# DC075B_TGC_SOURCE.net
KiCad netlist of a schematic drawn in Altium Designer
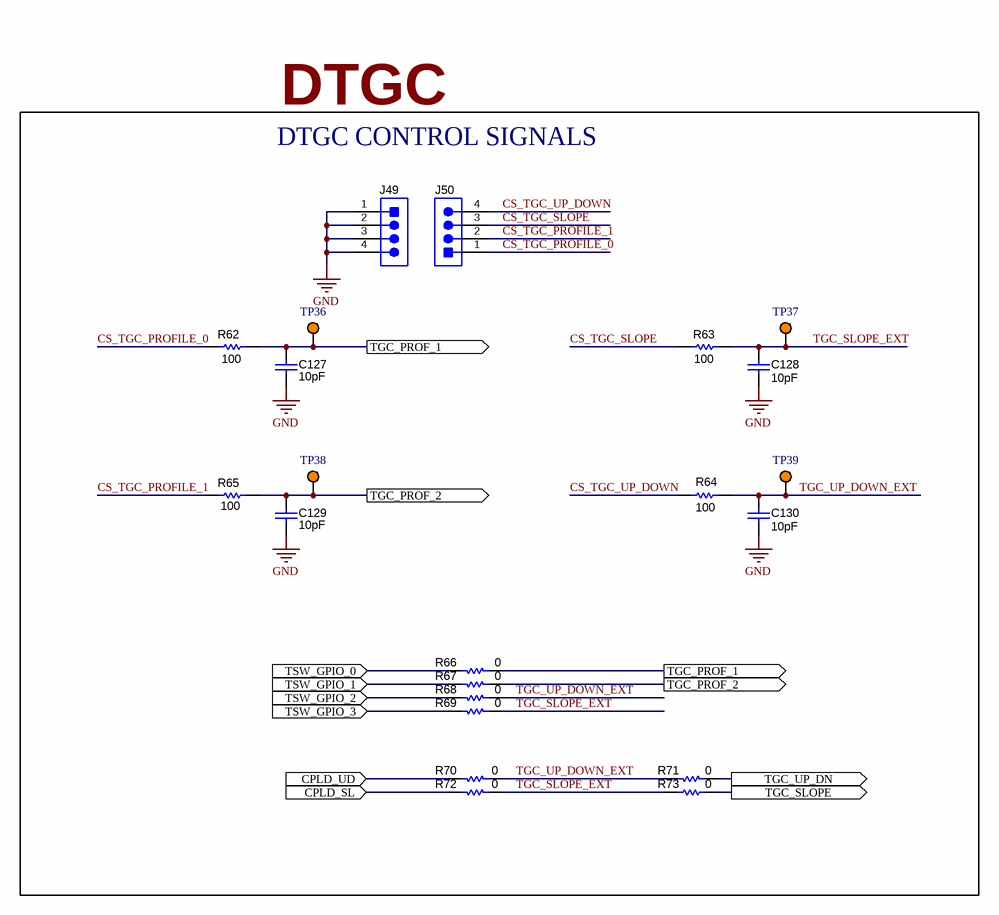
[diagram p0: DC075B_TGC_SOURCE.SchDoc]

(export (version "E")
  (design (tool "Eeschema 10.0.6"))
  (components
    (comp (ref "C127")
      (value "C0402C100C8GACTU")
      (footprint "0402")
      (description "CAP, CERM, 10 pF, 10 V,+/- 2.5%, C0G/NP0, 0402")
      (fields
        (field (name "MANUFACTURER") "Kemet")
        (field (name "VALUEDISPLAYED") "10pF")
        (field (name "PUBLISHER") "Texas Instruments")
      )
      (libsource (lib "Altium Vault - TI") (part "CMP-0064914-2"))
    )
    (comp (ref "C128")
      (value "10pF")
      (footprint "0402")
      (description "CAP, CERM, 10 pF, 50 V, +/- 5%, C0G/NP0, 0402")
      (fields
        (field (name "PARTNUMBER") "GRM1555C1H100JA01D")
        (field (name "MANUFACTURER") "MuRata")
        (field (name "PUBLISHER") "Texas Instruments")
      )
      (libsource (lib "Altium Vault - TI") (part "Capacitor"))
    )
    (comp (ref "C129")
      (value "C0402C100C8GACTU")
      (footprint "0402")
      (description "CAP, CERM, 10 pF, 10 V,+/- 2.5%, C0G/NP0, 0402")
      (fields
        (field (name "MANUFACTURER") "Kemet")
        (field (name "VALUEDISPLAYED") "10pF")
        (field (name "PUBLISHER") "Texas Instruments")
      )
      (libsource (lib "Altium Vault - TI") (part "CMP-0064914-2"))
    )
    (comp (ref "C130")
      (value "10pF")
      (footprint "0402")
      (description "CAP, CERM, 10 pF, 50 V, +/- 5%, C0G/NP0, 0402")
      (fields
        (field (name "PARTNUMBER") "GRM1555C1H100JA01D")
        (field (name "MANUFACTURER") "MuRata")
        (field (name "PUBLISHER") "Texas Instruments")
      )
      (libsource (lib "Altium Vault - TI") (part "Capacitor"))
    )
    (comp (ref "J49")
      (value "Header_4x1")
      (footprint "TSW-104-07-G-S")
      (description "Header, 100mil, 4x1, Gold, TH")
      (fields (field (name "PARTNUMBER") "TSW-104-07-G-S") (field (name "MANUFACTURER") "Samtec"))
      (libsource (lib "") (part "Header_4x1_1"))
    )
    (comp (ref "J50")
      (value "Header_4x1")
      (footprint "TSW-104-07-G-S")
      (description "Header, 100mil, 4x1, Gold, TH")
      (fields (field (name "PARTNUMBER") "TSW-104-07-G-S") (field (name "MANUFACTURER") "Samtec"))
      (libsource (lib "Altium Vault - TI") (part "Header_4x1"))
    )
    (comp (ref "R62")
      (value "100")
      (footprint "0603")
      (description "RES, 100, 1%, 0.1 W, AEC-Q200 Grade 0, 0603")
      (fields (field (name "MANUFACTURER") "Vishay-Dale") (field (name "PARTNUMBER") "CRCW0603100RFKEA"))
      (libsource (lib "Altium Vault - TI") (part "Resistor"))
    )
    (comp (ref "R63")
      (value "100")
      (footprint "0603")
      (description "RES, 100, 1%, 0.1 W, AEC-Q200 Grade 0, 0603")
      (fields (field (name "MANUFACTURER") "Vishay-Dale") (field (name "PARTNUMBER") "CRCW0603100RFKEA"))
      (libsource (lib "Altium Vault - TI") (part "Resistor"))
    )
    (comp (ref "R64")
      (value "100")
      (footprint "0603")
      (description "RES, 100, 1%, 0.1 W, AEC-Q200 Grade 0, 0603")
      (fields (field (name "MANUFACTURER") "Vishay-Dale") (field (name "PARTNUMBER") "CRCW0603100RFKEA"))
      (libsource (lib "Altium Vault - TI") (part "Resistor"))
    )
    (comp (ref "R65")
      (value "100")
      (footprint "0603")
      (description "RES, 100, 1%, 0.1 W, AEC-Q200 Grade 0, 0603")
      (fields (field (name "MANUFACTURER") "Vishay-Dale") (field (name "PARTNUMBER") "CRCW0603100RFKEA"))
      (libsource (lib "Altium Vault - TI") (part "Resistor"))
    )
    (comp (ref "R66")
      (value "0")
      (footprint "0402")
      (description "RES, 0, 5%, 0.063 W, AEC-Q200 Grade 0, 0402")
      (fields (field (name "MANUFACTURER") "Vishay-Dale") (field (name "PARTNUMBER") "CRCW04020000Z0ED"))
      (libsource (lib "Altium Vault - TI") (part "Resistor"))
    )
    (comp (ref "R67")
      (value "0")
      (footprint "0402")
      (description "RES, 0, 5%, 0.063 W, AEC-Q200 Grade 0, 0402")
      (fields (field (name "MANUFACTURER") "Vishay-Dale") (field (name "PARTNUMBER") "CRCW04020000Z0ED"))
      (libsource (lib "Altium Vault - TI") (part "Resistor"))
    )
    (comp (ref "R68")
      (value "0")
      (footprint "0402")
      (description "RES, 0, 5%, 0.063 W, AEC-Q200 Grade 0, 0402")
      (fields (field (name "MANUFACTURER") "Vishay-Dale") (field (name "PARTNUMBER") "CRCW04020000Z0ED"))
      (libsource (lib "Altium Vault - TI") (part "Resistor"))
    )
    (comp (ref "R69")
      (value "0")
      (footprint "0402")
      (description "RES, 0, 5%, 0.063 W, AEC-Q200 Grade 0, 0402")
      (fields (field (name "MANUFACTURER") "Vishay-Dale") (field (name "PARTNUMBER") "CRCW04020000Z0ED"))
      (libsource (lib "Altium Vault - TI") (part "Resistor"))
    )
    (comp (ref "R70")
      (value "0")
      (footprint "0402")
      (description "RES, 0, 5%, 0.063 W, AEC-Q200 Grade 0, 0402")
      (fields (field (name "MANUFACTURER") "Vishay-Dale") (field (name "PARTNUMBER") "CRCW04020000Z0ED"))
      (libsource (lib "Altium Vault - TI") (part "Resistor"))
    )
    (comp (ref "R71")
      (value "0")
      (footprint "0402")
      (description "RES, 0, 5%, 0.063 W, AEC-Q200 Grade 0, 0402")
      (fields (field (name "MANUFACTURER") "Vishay-Dale") (field (name "PARTNUMBER") "CRCW04020000Z0ED"))
      (libsource (lib "Altium Vault - TI") (part "Resistor"))
    )
    (comp (ref "R72")
      (value "0")
      (footprint "0402")
      (description "RES, 0, 5%, 0.063 W, AEC-Q200 Grade 0, 0402")
      (fields (field (name "MANUFACTURER") "Vishay-Dale") (field (name "PARTNUMBER") "CRCW04020000Z0ED"))
      (libsource (lib "Altium Vault - TI") (part "Resistor"))
    )
    (comp (ref "R73")
      (value "0")
      (footprint "0402")
      (description "RES, 0, 5%, 0.063 W, AEC-Q200 Grade 0, 0402")
      (fields (field (name "MANUFACTURER") "Vishay-Dale") (field (name "PARTNUMBER") "CRCW04020000Z0ED"))
      (libsource (lib "Altium Vault - TI") (part "Resistor"))
    )
    (comp (ref "TP36")
      (value "5003")
      (footprint "Keystone5003")
      (description "Test Point, Miniature, Orange, TH")
      (fields (field (name "MANUFACTURER") "Keystone") (field (name "PUBLISHER") "Texas Instruments"))
      (libsource (lib "Altium Vault - TI") (part "5003"))
    )
    (comp (ref "TP37")
      (value "5003")
      (footprint "Keystone5003")
      (description "Test Point, Miniature, Orange, TH")
      (fields (field (name "MANUFACTURER") "Keystone") (field (name "PUBLISHER") "Texas Instruments"))
      (libsource (lib "Altium Vault - TI") (part "5003"))
    )
    (comp (ref "TP38")
      (value "5003")
      (footprint "Keystone5003")
      (description "Test Point, Miniature, Orange, TH")
      (fields (field (name "MANUFACTURER") "Keystone") (field (name "PUBLISHER") "Texas Instruments"))
      (libsource (lib "Altium Vault - TI") (part "5003"))
    )
    (comp (ref "TP39")
      (value "5003")
      (footprint "Keystone5003")
      (description "Test Point, Miniature, Orange, TH")
      (fields (field (name "MANUFACTURER") "Keystone") (field (name "PUBLISHER") "Texas Instruments"))
      (libsource (lib "Altium Vault - TI") (part "5003"))
    )
  )
  (nets
    (net (code "1") (name "/CPLD_SL") (class "Default")
      (node (ref "R72") (pin "1") (pinfunction "1_1") (pintype "passive"))
    )
    (net (code "2") (name "/CPLD_UD") (class "Default")
      (node (ref "R70") (pin "1") (pinfunction "1_1") (pintype "passive"))
    )
    (net (code "3") (name "/CS_TGC_PROFILE_0") (class "Default")
      (node (ref "J50") (pin "1") (pinfunction "1_1") (pintype "passive"))
      (node (ref "R62") (pin "1") (pinfunction "1_1") (pintype "passive"))
    )
    (net (code "4") (name "/CS_TGC_PROFILE_1") (class "Default")
      (node (ref "J50") (pin "2") (pinfunction "2_2") (pintype "passive"))
      (node (ref "R65") (pin "1") (pinfunction "1_1") (pintype "passive"))
    )
    (net (code "5") (name "/CS_TGC_SLOPE") (class "Default")
      (node (ref "J50") (pin "3") (pinfunction "3_3") (pintype "passive"))
      (node (ref "R63") (pin "1") (pinfunction "1_1") (pintype "passive"))
    )
    (net (code "6") (name "/CS_TGC_UP_DOWN") (class "Default")
      (node (ref "J50") (pin "4") (pinfunction "4_4") (pintype "passive"))
      (node (ref "R64") (pin "1") (pinfunction "1_1") (pintype "passive"))
    )
    (net (code "7") (name "/TGC_PROF_1") (class "Default")
      (node (ref "C127") (pin "1") (pinfunction "1_1") (pintype "passive"))
      (node (ref "R62") (pin "2") (pinfunction "2_2") (pintype "passive"))
      (node (ref "R66") (pin "2") (pinfunction "2_2") (pintype "passive"))
      (node (ref "TP36") (pin "1") (pintype "passive"))
    )
    (net (code "8") (name "/TGC_PROF_2") (class "Default")
      (node (ref "C129") (pin "1") (pinfunction "1_1") (pintype "passive"))
      (node (ref "R65") (pin "2") (pinfunction "2_2") (pintype "passive"))
      (node (ref "R67") (pin "2") (pinfunction "2_2") (pintype "passive"))
      (node (ref "TP38") (pin "1") (pintype "passive"))
    )
    (net (code "9") (name "/TGC_SLOPE") (class "Default")
      (node (ref "R73") (pin "1") (pinfunction "1_1") (pintype "passive"))
    )
    (net (code "10") (name "/TGC_SLOPE_EXT") (class "Default")
      (node (ref "C128") (pin "1") (pinfunction "1_1") (pintype "passive"))
      (node (ref "R63") (pin "2") (pinfunction "2_2") (pintype "passive"))
      (node (ref "R69") (pin "2") (pinfunction "2_2") (pintype "passive"))
      (node (ref "R72") (pin "2") (pinfunction "2_2") (pintype "passive"))
      (node (ref "R73") (pin "2") (pinfunction "2_2") (pintype "passive"))
      (node (ref "TP37") (pin "1") (pintype "passive"))
    )
    (net (code "11") (name "/TGC_UP_DN") (class "Default")
      (node (ref "R71") (pin "1") (pinfunction "1_1") (pintype "passive"))
    )
    (net (code "12") (name "/TGC_UP_DOWN_EXT") (class "Default")
      (node (ref "C130") (pin "1") (pinfunction "1_1") (pintype "passive"))
      (node (ref "R64") (pin "2") (pinfunction "2_2") (pintype "passive"))
      (node (ref "R68") (pin "2") (pinfunction "2_2") (pintype "passive"))
      (node (ref "R70") (pin "2") (pinfunction "2_2") (pintype "passive"))
      (node (ref "R71") (pin "2") (pinfunction "2_2") (pintype "passive"))
      (node (ref "TP39") (pin "1") (pintype "passive"))
    )
    (net (code "13") (name "/TSW_GPIO_0") (class "Default")
      (node (ref "R66") (pin "1") (pinfunction "1_1") (pintype "passive"))
    )
    (net (code "14") (name "/TSW_GPIO_1") (class "Default")
      (node (ref "R67") (pin "1") (pinfunction "1_1") (pintype "passive"))
    )
    (net (code "15") (name "/TSW_GPIO_2") (class "Default")
      (node (ref "R68") (pin "1") (pinfunction "1_1") (pintype "passive"))
    )
    (net (code "16") (name "/TSW_GPIO_3") (class "Default")
      (node (ref "R69") (pin "1") (pinfunction "1_1") (pintype "passive"))
    )
    (net (code "17") (name "GND") (class "Default")
      (node (ref "C127") (pin "2") (pinfunction "2_2") (pintype "passive"))
      (node (ref "C128") (pin "2") (pinfunction "2_2") (pintype "passive"))
      (node (ref "C129") (pin "2") (pinfunction "2_2") (pintype "passive"))
      (node (ref "C130") (pin "2") (pinfunction "2_2") (pintype "passive"))
      (node (ref "J49") (pin "1") (pinfunction "1_1") (pintype "passive"))
      (node (ref "J49") (pin "2") (pinfunction "2_2") (pintype "passive"))
      (node (ref "J49") (pin "3") (pinfunction "3_3") (pintype "passive"))
      (node (ref "J49") (pin "4") (pinfunction "4_4") (pintype "passive"))
    )
  )
)
